# ASD2005.net
KiCad netlist of a schematic drawn in EAGLE
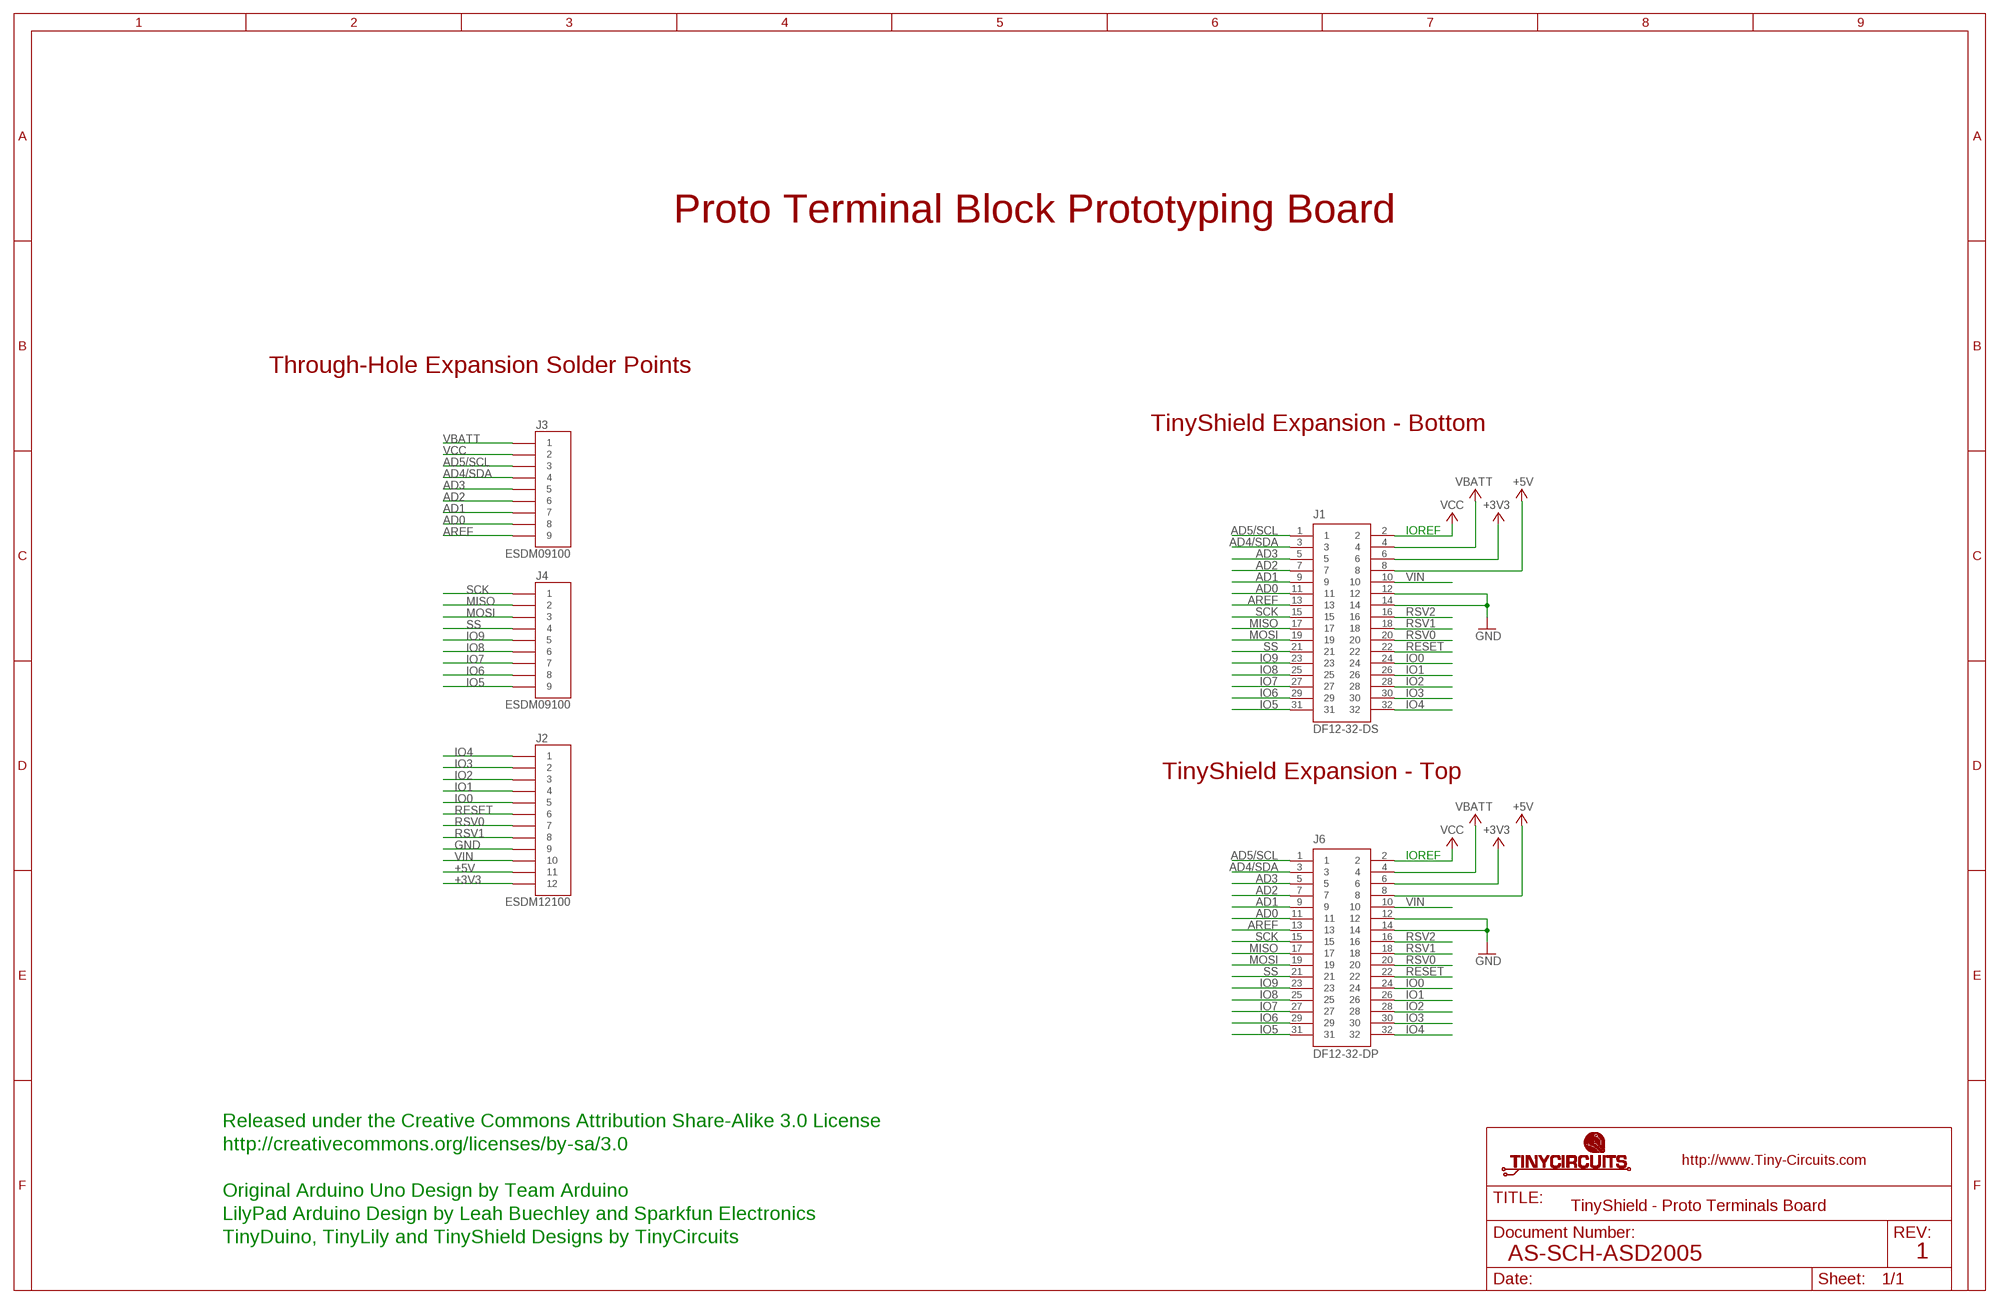
[diagram p0: schematic, sheet 1]

(export (version "E")
  (design (tool "Eeschema 10.0.6"))
  (components
    (comp (ref "J1")
      (value "DF12-32-DS")
      (footprint "eagle-import:DF12-32-DS")
      (fields (field (name "PARTNO") "AS-ITM-00012") (field (name "PARTNO_1") "AS-ITM-00012"))
      (libsource (lib "eagle-import") (part "AS-ITM-00012"))
    )
    (comp (ref "J2")
      (value "ESDM12100")
      (footprint "eagle-import:12POS_2.54MM_TERMBLOCK")
      (fields (field (name "PARTNO") "AS-ITM-00123"))
      (libsource (lib "eagle-import") (part "AS-ITM-00123"))
    )
    (comp (ref "J3")
      (value "ESDM09100")
      (footprint "eagle-import:9POS_2.54MM_TERMBLOCK")
      (fields (field (name "PARTNO") "AS-ITM-00124"))
      (libsource (lib "eagle-import") (part "AS-ITM-00124"))
    )
    (comp (ref "J4")
      (value "ESDM09100")
      (footprint "eagle-import:9POS_2.54MM_TERMBLOCK")
      (fields (field (name "PARTNO") "AS-ITM-00124"))
      (libsource (lib "eagle-import") (part "AS-ITM-00124"))
    )
    (comp (ref "J6")
      (value "DF12-32-DP")
      (footprint "eagle-import:DF12-32-DP")
      (fields (field (name "PARTNO") "AS-ITM-00015") (field (name "PARTNO_1") "AS-ITM-00015"))
      (libsource (lib "eagle-import") (part "AS-ITM-00015"))
    )
  )
  (nets
    (net (code "1") (name "+3V3") (class "Default")
      (node (ref "J1") (pin "6") (pinfunction "6_6") (pintype "bidirectional"))
      (node (ref "J2") (pin "P$13") (pinfunction "12_P$13") (pintype "bidirectional"))
      (node (ref "J6") (pin "6") (pinfunction "6_6") (pintype "bidirectional"))
    )
    (net (code "2") (name "+5V") (class "Default")
      (node (ref "J1") (pin "8") (pinfunction "8_8") (pintype "bidirectional"))
      (node (ref "J2") (pin "P$12") (pinfunction "11_P$12") (pintype "bidirectional"))
      (node (ref "J6") (pin "8") (pinfunction "8_8") (pintype "bidirectional"))
    )
    (net (code "3") (name "/AD0") (class "Default")
      (node (ref "J1") (pin "11") (pinfunction "11_11") (pintype "bidirectional"))
      (node (ref "J3") (pin "P$8") (pinfunction "8_P$8") (pintype "bidirectional"))
      (node (ref "J6") (pin "11") (pinfunction "11_11") (pintype "bidirectional"))
    )
    (net (code "4") (name "/AD1") (class "Default")
      (node (ref "J1") (pin "9") (pinfunction "9_9") (pintype "bidirectional"))
      (node (ref "J3") (pin "P$7") (pinfunction "7_P$7") (pintype "bidirectional"))
      (node (ref "J6") (pin "9") (pinfunction "9_9") (pintype "bidirectional"))
    )
    (net (code "5") (name "/AD2") (class "Default")
      (node (ref "J1") (pin "7") (pinfunction "7_7") (pintype "bidirectional"))
      (node (ref "J3") (pin "P$6") (pinfunction "6_P$6") (pintype "bidirectional"))
      (node (ref "J6") (pin "7") (pinfunction "7_7") (pintype "bidirectional"))
    )
    (net (code "6") (name "/AD3") (class "Default")
      (node (ref "J1") (pin "5") (pinfunction "5_5") (pintype "bidirectional"))
      (node (ref "J3") (pin "P$5") (pinfunction "5_P$5") (pintype "bidirectional"))
      (node (ref "J6") (pin "5") (pinfunction "5_5") (pintype "bidirectional"))
    )
    (net (code "7") (name "/AD4{slash}SDA") (class "Default")
      (node (ref "J1") (pin "3") (pinfunction "3_3") (pintype "bidirectional"))
      (node (ref "J3") (pin "P$4") (pinfunction "4_P$4") (pintype "bidirectional"))
      (node (ref "J6") (pin "3") (pinfunction "3_3") (pintype "bidirectional"))
    )
    (net (code "8") (name "/AD5{slash}SCL") (class "Default")
      (node (ref "J1") (pin "1") (pinfunction "1_1") (pintype "bidirectional"))
      (node (ref "J3") (pin "P$3") (pinfunction "3_P$3") (pintype "bidirectional"))
      (node (ref "J6") (pin "1") (pinfunction "1_1") (pintype "bidirectional"))
    )
    (net (code "9") (name "/AREF") (class "Default")
      (node (ref "J1") (pin "13") (pinfunction "13_13") (pintype "bidirectional"))
      (node (ref "J3") (pin "P$9") (pinfunction "9_P$9") (pintype "bidirectional"))
      (node (ref "J6") (pin "13") (pinfunction "13_13") (pintype "bidirectional"))
    )
    (net (code "10") (name "/IO0") (class "Default")
      (node (ref "J1") (pin "24") (pinfunction "24_24") (pintype "bidirectional"))
      (node (ref "J2") (pin "P$5") (pinfunction "5_P$5") (pintype "bidirectional"))
      (node (ref "J6") (pin "24") (pinfunction "24_24") (pintype "bidirectional"))
    )
    (net (code "11") (name "/IO1") (class "Default")
      (node (ref "J1") (pin "26") (pinfunction "26_26") (pintype "bidirectional"))
      (node (ref "J2") (pin "P$4") (pinfunction "4_P$4") (pintype "bidirectional"))
      (node (ref "J6") (pin "26") (pinfunction "26_26") (pintype "bidirectional"))
    )
    (net (code "12") (name "/IO2") (class "Default")
      (node (ref "J1") (pin "28") (pinfunction "28_28") (pintype "bidirectional"))
      (node (ref "J2") (pin "P$3") (pinfunction "3_P$3") (pintype "bidirectional"))
      (node (ref "J6") (pin "28") (pinfunction "28_28") (pintype "bidirectional"))
    )
    (net (code "13") (name "/IO3") (class "Default")
      (node (ref "J1") (pin "30") (pinfunction "30_30") (pintype "bidirectional"))
      (node (ref "J2") (pin "P$2") (pinfunction "2_P$2") (pintype "bidirectional"))
      (node (ref "J6") (pin "30") (pinfunction "30_30") (pintype "bidirectional"))
    )
    (net (code "14") (name "/IO4") (class "Default")
      (node (ref "J1") (pin "32") (pinfunction "32_32") (pintype "bidirectional"))
      (node (ref "J2") (pin "P$1") (pinfunction "1_P$1") (pintype "bidirectional"))
      (node (ref "J6") (pin "32") (pinfunction "32_32") (pintype "bidirectional"))
    )
    (net (code "15") (name "/IO5") (class "Default")
      (node (ref "J1") (pin "31") (pinfunction "31_31") (pintype "bidirectional"))
      (node (ref "J4") (pin "P$9") (pinfunction "9_P$9") (pintype "bidirectional"))
      (node (ref "J6") (pin "31") (pinfunction "31_31") (pintype "bidirectional"))
    )
    (net (code "16") (name "/IO6") (class "Default")
      (node (ref "J1") (pin "29") (pinfunction "29_29") (pintype "bidirectional"))
      (node (ref "J4") (pin "P$8") (pinfunction "8_P$8") (pintype "bidirectional"))
      (node (ref "J6") (pin "29") (pinfunction "29_29") (pintype "bidirectional"))
    )
    (net (code "17") (name "/IO7") (class "Default")
      (node (ref "J1") (pin "27") (pinfunction "27_27") (pintype "bidirectional"))
      (node (ref "J4") (pin "P$7") (pinfunction "7_P$7") (pintype "bidirectional"))
      (node (ref "J6") (pin "27") (pinfunction "27_27") (pintype "bidirectional"))
    )
    (net (code "18") (name "/IO8") (class "Default")
      (node (ref "J1") (pin "25") (pinfunction "25_25") (pintype "bidirectional"))
      (node (ref "J4") (pin "P$6") (pinfunction "6_P$6") (pintype "bidirectional"))
      (node (ref "J6") (pin "25") (pinfunction "25_25") (pintype "bidirectional"))
    )
    (net (code "19") (name "/IO9") (class "Default")
      (node (ref "J1") (pin "23") (pinfunction "23_23") (pintype "bidirectional"))
      (node (ref "J4") (pin "P$5") (pinfunction "5_P$5") (pintype "bidirectional"))
      (node (ref "J6") (pin "23") (pinfunction "23_23") (pintype "bidirectional"))
    )
    (net (code "20") (name "/MISO") (class "Default")
      (node (ref "J1") (pin "17") (pinfunction "17_17") (pintype "bidirectional"))
      (node (ref "J4") (pin "P$2") (pinfunction "2_P$2") (pintype "bidirectional"))
      (node (ref "J6") (pin "17") (pinfunction "17_17") (pintype "bidirectional"))
    )
    (net (code "21") (name "/MOSI") (class "Default")
      (node (ref "J1") (pin "19") (pinfunction "19_19") (pintype "bidirectional"))
      (node (ref "J4") (pin "P$3") (pinfunction "3_P$3") (pintype "bidirectional"))
      (node (ref "J6") (pin "19") (pinfunction "19_19") (pintype "bidirectional"))
    )
    (net (code "22") (name "/RESET") (class "Default")
      (node (ref "J1") (pin "22") (pinfunction "22_22") (pintype "bidirectional"))
      (node (ref "J2") (pin "P$6") (pinfunction "6_P$6") (pintype "bidirectional"))
      (node (ref "J6") (pin "22") (pinfunction "22_22") (pintype "bidirectional"))
    )
    (net (code "23") (name "/RSV0") (class "Default")
      (node (ref "J1") (pin "20") (pinfunction "20_20") (pintype "bidirectional"))
      (node (ref "J2") (pin "P$7") (pinfunction "7_P$7") (pintype "bidirectional"))
      (node (ref "J6") (pin "20") (pinfunction "20_20") (pintype "bidirectional"))
    )
    (net (code "24") (name "/RSV1") (class "Default")
      (node (ref "J1") (pin "18") (pinfunction "18_18") (pintype "bidirectional"))
      (node (ref "J2") (pin "P$8") (pinfunction "8_P$8") (pintype "bidirectional"))
      (node (ref "J6") (pin "18") (pinfunction "18_18") (pintype "bidirectional"))
    )
    (net (code "25") (name "/RSV2") (class "Default")
      (node (ref "J1") (pin "16") (pinfunction "16_16") (pintype "bidirectional"))
      (node (ref "J6") (pin "16") (pinfunction "16_16") (pintype "bidirectional"))
    )
    (net (code "26") (name "/SCK") (class "Default")
      (node (ref "J1") (pin "15") (pinfunction "15_15") (pintype "bidirectional"))
      (node (ref "J4") (pin "P$1") (pinfunction "1_P$1") (pintype "bidirectional"))
      (node (ref "J6") (pin "15") (pinfunction "15_15") (pintype "bidirectional"))
    )
    (net (code "27") (name "/SS") (class "Default")
      (node (ref "J1") (pin "21") (pinfunction "21_21") (pintype "bidirectional"))
      (node (ref "J4") (pin "P$4") (pinfunction "4_P$4") (pintype "bidirectional"))
      (node (ref "J6") (pin "21") (pinfunction "21_21") (pintype "bidirectional"))
    )
    (net (code "28") (name "/VIN") (class "Default")
      (node (ref "J1") (pin "10") (pinfunction "10_10") (pintype "bidirectional"))
      (node (ref "J2") (pin "P$10") (pinfunction "10_P$10") (pintype "bidirectional"))
      (node (ref "J6") (pin "10") (pinfunction "10_10") (pintype "bidirectional"))
    )
    (net (code "29") (name "GND") (class "Default")
      (node (ref "J1") (pin "12") (pinfunction "12_12") (pintype "bidirectional"))
      (node (ref "J1") (pin "14") (pinfunction "14_14") (pintype "bidirectional"))
      (node (ref "J2") (pin "P$9") (pinfunction "9_P$9") (pintype "bidirectional"))
      (node (ref "J6") (pin "12") (pinfunction "12_12") (pintype "bidirectional"))
      (node (ref "J6") (pin "14") (pinfunction "14_14") (pintype "bidirectional"))
    )
    (net (code "30") (name "VBATT") (class "Default")
      (node (ref "J1") (pin "4") (pinfunction "4_4") (pintype "bidirectional"))
      (node (ref "J3") (pin "P$1") (pinfunction "1_P$1") (pintype "bidirectional"))
      (node (ref "J6") (pin "4") (pinfunction "4_4") (pintype "bidirectional"))
    )
    (net (code "31") (name "VCC") (class "Default")
      (node (ref "J1") (pin "2") (pinfunction "2_2") (pintype "bidirectional"))
      (node (ref "J3") (pin "P$2") (pinfunction "2_P$2") (pintype "bidirectional"))
      (node (ref "J6") (pin "2") (pinfunction "2_2") (pintype "bidirectional"))
    )
  )
)
